# MCU_POWER.net
KiCad netlist of a schematic drawn in Altium Designer
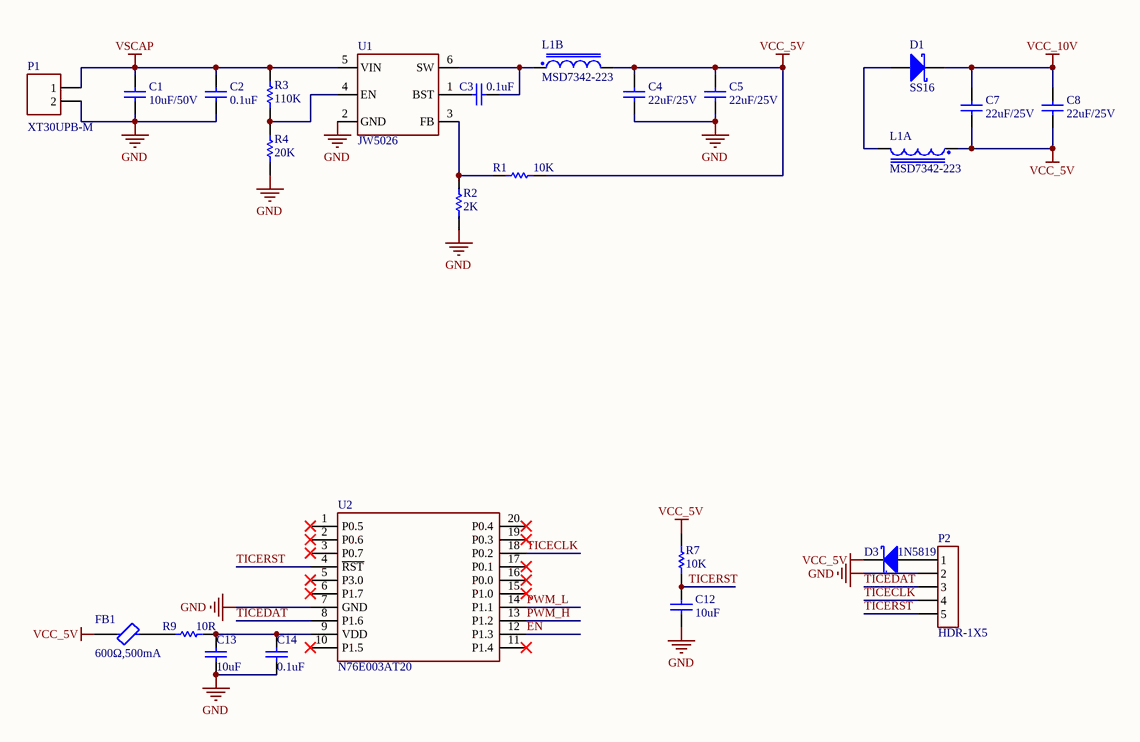
[diagram p0: MCU_POWER.SchDoc]

(export (version "E")
  (design (tool "Eeschema 10.0.6"))
  (components
    (comp (ref "C1")
      (value "10uF/50V")
      (footprint "C0805_M")
      (description "Capacitor")
      (libsource (lib "Miscellaneous Devices") (part "Cap"))
    )
    (comp (ref "C2")
      (value "0.1uF")
      (footprint "C0603_M")
      (description "Capacitor")
      (libsource (lib "Miscellaneous Devices") (part "Cap"))
    )
    (comp (ref "C3")
      (value "0.1uF")
      (footprint "C0603_M")
      (description "Capacitor")
      (libsource (lib "Miscellaneous Devices") (part "Cap"))
    )
    (comp (ref "C4")
      (value "22uF/25V")
      (footprint "C0805_M")
      (description "Capacitor")
      (libsource (lib "Miscellaneous Devices") (part "Cap"))
    )
    (comp (ref "C5")
      (value "22uF/25V")
      (footprint "C0805_M")
      (description "Capacitor")
      (libsource (lib "Miscellaneous Devices") (part "Cap"))
    )
    (comp (ref "C7")
      (value "22uF/25V")
      (footprint "C0805_M")
      (description "Capacitor")
      (libsource (lib "Miscellaneous Devices") (part "Cap"))
    )
    (comp (ref "C8")
      (value "22uF/25V")
      (footprint "C0805_M")
      (description "Capacitor")
      (libsource (lib "Miscellaneous Devices") (part "Cap"))
    )
    (comp (ref "C12")
      (value "10uF")
      (footprint "C0603_M")
      (description "Capacitor")
      (libsource (lib "Miscellaneous Devices") (part "Cap"))
    )
    (comp (ref "C13")
      (value "10uF")
      (footprint "C0603_M")
      (description "Capacitor")
      (libsource (lib "Miscellaneous Devices") (part "Cap"))
    )
    (comp (ref "C14")
      (value "0.1uF")
      (footprint "C0603_M")
      (description "Capacitor")
      (libsource (lib "Miscellaneous Devices") (part "Cap"))
    )
    (comp (ref "D1")
      (value "SS16")
      (footprint "SOD-123")
      (description "Schottky Diode")
      (fields (field (name "PUBLISHER") "Altium Limited"))
      (libsource (lib "my_library") (part "D Schottky"))
    )
    (comp (ref "D3")
      (value "1N5819")
      (footprint "SOD-323")
      (description "Schottky Diode")
      (fields (field (name "PUBLISHER") "Altium Limited"))
      (libsource (lib "my_library") (part "D Schottky"))
    )
    (comp (ref "FB1")
      (value "600Ω,500mA")
      (footprint "FB0603_M")
      (libsource (lib "my_library") (part "Ferrite Bead"))
    )
    (comp (ref "L1")
      (value "MSD7342-223")
      (footprint "MSD7342")
      (libsource (lib "") (part "Coupled Inductor_1"))
    )
    (comp (ref "P1")
      (value "XT30UPB-M")
      (footprint "XT30UPB-M")
      (libsource (lib "my_library") (part "XT30UPB-F"))
    )
    (comp (ref "P2")
      (value "HDR-1X5")
      (footprint "HDR2.54-LI-5P")
      (libsource (lib "my_library") (part "HDR-1X5"))
    )
    (comp (ref "R1")
      (value "10K")
      (footprint "R0603_M")
      (description "Resistor")
      (libsource (lib "Miscellaneous Devices") (part "Res1"))
    )
    (comp (ref "R2")
      (value "2K")
      (footprint "R0603_M")
      (description "Resistor")
      (libsource (lib "Miscellaneous Devices") (part "Res1"))
    )
    (comp (ref "R3")
      (value "110K")
      (footprint "R0603_M")
      (description "Resistor")
      (libsource (lib "Miscellaneous Devices") (part "Res1"))
    )
    (comp (ref "R4")
      (value "20K")
      (footprint "R0603_M")
      (description "Resistor")
      (libsource (lib "Miscellaneous Devices") (part "Res1"))
    )
    (comp (ref "R7")
      (value "10K")
      (footprint "R0603_M")
      (description "Resistor")
      (libsource (lib "Miscellaneous Devices") (part "Res1"))
    )
    (comp (ref "R9")
      (value "10R")
      (footprint "R0603_M")
      (description "Resistor")
      (libsource (lib "Miscellaneous Devices") (part "Res1"))
    )
    (comp (ref "U1")
      (value "JW5026")
      (footprint "2.07-SOT封装:SOT23-6N")
      (libsource (lib "my_library") (part "JW5026"))
    )
    (comp (ref "U2")
      (value "N76E003AT20")
      (footprint "TSSOP20_N")
      (libsource (lib "my_library") (part "N76E003AT20"))
    )
  )
  (nets
    (net (code "1") (name "/EN") (class "Default")
      (node (ref "U2") (pin "12") (pinfunction "P1.3_12") (pintype "passive"))
    )
    (net (code "2") (name "/PWM_H") (class "Default")
      (node (ref "U2") (pin "13") (pinfunction "P1.2_13") (pintype "passive"))
    )
    (net (code "3") (name "/PWM_L") (class "Default")
      (node (ref "U2") (pin "14") (pinfunction "P1.1_14") (pintype "passive"))
    )
    (net (code "4") (name "/TICECLK") (class "Default")
      (node (ref "P2") (pin "4") (pinfunction "4_4") (pintype "passive"))
      (node (ref "U2") (pin "18") (pinfunction "P0.2_18") (pintype "passive"))
    )
    (net (code "5") (name "/TICEDAT") (class "Default")
      (node (ref "P2") (pin "3") (pinfunction "3_3") (pintype "passive"))
      (node (ref "U2") (pin "8") (pinfunction "P1.6_8") (pintype "passive"))
    )
    (net (code "6") (name "/TICERST") (class "Default")
      (node (ref "C12") (pin "2") (pinfunction "2_2") (pintype "passive"))
      (node (ref "P2") (pin "5") (pinfunction "5_5") (pintype "passive"))
      (node (ref "R7") (pin "2") (pinfunction "2_2") (pintype "passive"))
      (node (ref "U2") (pin "4") (pinfunction "~{RST}_4") (pintype "passive"))
    )
    (net (code "7") (name "GND") (class "Default")
      (node (ref "C1") (pin "1") (pinfunction "1_1") (pintype "passive"))
      (node (ref "C12") (pin "1") (pinfunction "1_1") (pintype "passive"))
      (node (ref "C13") (pin "1") (pinfunction "1_1") (pintype "passive"))
      (node (ref "C14") (pin "1") (pinfunction "1_1") (pintype "passive"))
      (node (ref "C2") (pin "1") (pinfunction "1_1") (pintype "passive"))
      (node (ref "C4") (pin "1") (pinfunction "1_1") (pintype "passive"))
      (node (ref "C5") (pin "1") (pinfunction "1_1") (pintype "passive"))
      (node (ref "P1") (pin "2") (pinfunction "2_2") (pintype "passive"))
      (node (ref "P2") (pin "2") (pinfunction "2_2") (pintype "passive"))
      (node (ref "R2") (pin "2") (pinfunction "2_2") (pintype "passive"))
      (node (ref "R4") (pin "2") (pinfunction "2_2") (pintype "passive"))
      (node (ref "U1") (pin "2") (pinfunction "GND_2") (pintype "passive"))
      (node (ref "U2") (pin "7") (pinfunction "GND_7") (pintype "power_in"))
    )
    (net (code "8") (name "Net-(D1-A)") (class "Default")
      (node (ref "D1") (pin "1") (pinfunction "A_1") (pintype "passive"))
      (node (ref "L1") (pin "3") (pinfunction "3_3") (pintype "passive"))
    )
    (net (code "9") (name "Net-(D3-A)") (class "Default")
      (node (ref "D3") (pin "1") (pinfunction "A_1") (pintype "passive"))
      (node (ref "P2") (pin "1") (pinfunction "1_1") (pintype "passive"))
    )
    (net (code "10") (name "Net-(FB1-Pad2)") (class "Default")
      (node (ref "FB1") (pin "2") (pinfunction "2_2") (pintype "passive"))
      (node (ref "R9") (pin "1") (pinfunction "1_1") (pintype "passive"))
    )
    (net (code "11") (name "Net-(U1-BST)") (class "Default")
      (node (ref "C3") (pin "1") (pinfunction "1_1") (pintype "passive"))
      (node (ref "U1") (pin "1") (pinfunction "BST_1") (pintype "passive"))
    )
    (net (code "12") (name "Net-(U1-EN)") (class "Default")
      (node (ref "R3") (pin "1") (pinfunction "1_1") (pintype "passive"))
      (node (ref "R4") (pin "1") (pinfunction "1_1") (pintype "passive"))
      (node (ref "U1") (pin "4") (pinfunction "EN_4") (pintype "passive"))
    )
    (net (code "13") (name "Net-(U1-FB)") (class "Default")
      (node (ref "R1") (pin "1") (pinfunction "1_1") (pintype "passive"))
      (node (ref "R2") (pin "1") (pinfunction "1_1") (pintype "passive"))
      (node (ref "U1") (pin "3") (pinfunction "FB_3") (pintype "passive"))
    )
    (net (code "14") (name "Net-(U1-SW)") (class "Default")
      (node (ref "C3") (pin "2") (pinfunction "2_2") (pintype "passive"))
      (node (ref "L1") (pin "2") (pinfunction "2_2") (pintype "passive"))
      (node (ref "U1") (pin "6") (pinfunction "SW_6") (pintype "passive"))
    )
    (net (code "15") (name "Net-(U2-VDD)") (class "Default")
      (node (ref "C13") (pin "2") (pinfunction "2_2") (pintype "passive"))
      (node (ref "C14") (pin "2") (pinfunction "2_2") (pintype "passive"))
      (node (ref "R9") (pin "2") (pinfunction "2_2") (pintype "passive"))
      (node (ref "U2") (pin "9") (pinfunction "VDD_9") (pintype "power_in"))
    )
    (net (code "16") (name "VCC_5V") (class "Default")
      (node (ref "C4") (pin "2") (pinfunction "2_2") (pintype "passive"))
      (node (ref "C5") (pin "2") (pinfunction "2_2") (pintype "passive"))
      (node (ref "C7") (pin "1") (pinfunction "1_1") (pintype "passive"))
      (node (ref "C8") (pin "1") (pinfunction "1_1") (pintype "passive"))
      (node (ref "D3") (pin "2") (pinfunction "K_2") (pintype "passive"))
      (node (ref "FB1") (pin "1") (pinfunction "1_1") (pintype "passive"))
      (node (ref "L1") (pin "1") (pinfunction "1_1") (pintype "passive"))
      (node (ref "L1") (pin "4") (pinfunction "4_4") (pintype "passive"))
      (node (ref "R1") (pin "2") (pinfunction "2_2") (pintype "passive"))
      (node (ref "R7") (pin "1") (pinfunction "1_1") (pintype "passive"))
    )
    (net (code "17") (name "VCC_10V") (class "Default")
      (node (ref "C7") (pin "2") (pinfunction "2_2") (pintype "passive"))
      (node (ref "C8") (pin "2") (pinfunction "2_2") (pintype "passive"))
      (node (ref "D1") (pin "2") (pinfunction "K_2") (pintype "passive"))
    )
    (net (code "18") (name "VSCAP") (class "Default")
      (node (ref "C1") (pin "2") (pinfunction "2_2") (pintype "passive"))
      (node (ref "C2") (pin "2") (pinfunction "2_2") (pintype "passive"))
      (node (ref "P1") (pin "1") (pinfunction "1_1") (pintype "passive"))
      (node (ref "R3") (pin "2") (pinfunction "2_2") (pintype "passive"))
      (node (ref "U1") (pin "5") (pinfunction "VIN_5") (pintype "passive"))
    )
    (net (code "19") (name "unconnected-(U2-P0.0-Pad16)") (class "Default")
      (node (ref "U2") (pin "16") (pinfunction "P0.0_16") (pintype "passive+no_connect"))
    )
    (net (code "20") (name "unconnected-(U2-P0.1-Pad17)") (class "Default")
      (node (ref "U2") (pin "17") (pinfunction "P0.1_17") (pintype "passive+no_connect"))
    )
    (net (code "21") (name "unconnected-(U2-P0.3-Pad19)") (class "Default")
      (node (ref "U2") (pin "19") (pinfunction "P0.3_19") (pintype "passive+no_connect"))
    )
    (net (code "22") (name "unconnected-(U2-P0.4-Pad20)") (class "Default")
      (node (ref "U2") (pin "20") (pinfunction "P0.4_20") (pintype "passive+no_connect"))
    )
    (net (code "23") (name "unconnected-(U2-P0.5-Pad1)") (class "Default")
      (node (ref "U2") (pin "1") (pinfunction "P0.5_1") (pintype "passive+no_connect"))
    )
    (net (code "24") (name "unconnected-(U2-P0.6-Pad2)") (class "Default")
      (node (ref "U2") (pin "2") (pinfunction "P0.6_2") (pintype "passive+no_connect"))
    )
    (net (code "25") (name "unconnected-(U2-P0.7-Pad3)") (class "Default")
      (node (ref "U2") (pin "3") (pinfunction "P0.7_3") (pintype "passive+no_connect"))
    )
    (net (code "26") (name "unconnected-(U2-P1.0-Pad15)") (class "Default")
      (node (ref "U2") (pin "15") (pinfunction "P1.0_15") (pintype "passive+no_connect"))
    )
    (net (code "27") (name "unconnected-(U2-P1.4-Pad11)") (class "Default")
      (node (ref "U2") (pin "11") (pinfunction "P1.4_11") (pintype "passive+no_connect"))
    )
    (net (code "28") (name "unconnected-(U2-P1.5-Pad10)") (class "Default")
      (node (ref "U2") (pin "10") (pinfunction "P1.5_10") (pintype "passive+no_connect"))
    )
    (net (code "29") (name "unconnected-(U2-P1.7-Pad6)") (class "Default")
      (node (ref "U2") (pin "6") (pinfunction "P1.7_6") (pintype "passive+no_connect"))
    )
    (net (code "30") (name "unconnected-(U2-P3.0-Pad5)") (class "Default")
      (node (ref "U2") (pin "5") (pinfunction "P3.0_5") (pintype "passive+no_connect"))
    )
  )
)
